# button.net
KiCad netlist of a schematic drawn in EAGLE
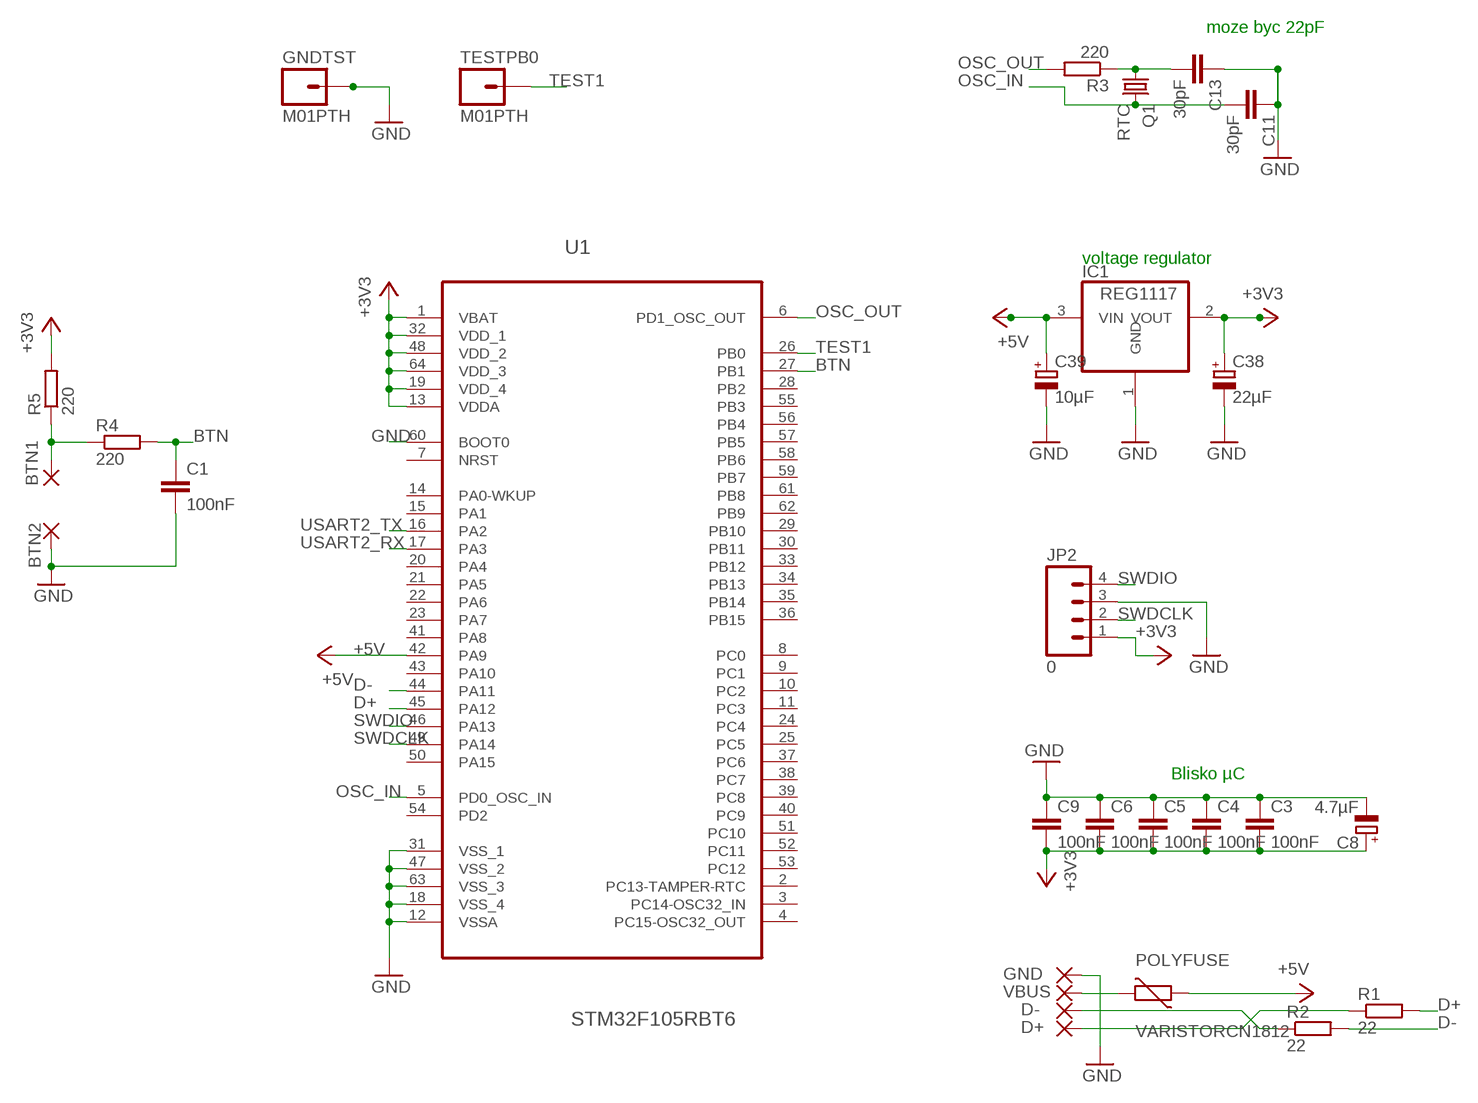
[diagram p0: schematic, sheet 1]

(export (version "E")
  (design (tool "Eeschema 10.0.6"))
  (components
    (comp (ref "BTN1")
      (value "1,6/0,8")
      (footprint "eagle-import:1,6_0,8")
      (libsource (lib "eagle-import") (part "1,6/0,8"))
    )
    (comp (ref "BTN2")
      (value "1,6/0,8")
      (footprint "eagle-import:1,6_0,8")
      (libsource (lib "eagle-import") (part "1,6/0,8"))
    )
    (comp (ref "C1")
      (value "100nF")
      (footprint "eagle-import:C0603")
      (libsource (lib "eagle-import") (part "C-EUC0603"))
    )
    (comp (ref "C3")
      (value "100nF")
      (footprint "eagle-import:C0603")
      (libsource (lib "eagle-import") (part "C-EUC0603"))
    )
    (comp (ref "C4")
      (value "100nF")
      (footprint "eagle-import:C0603")
      (libsource (lib "eagle-import") (part "C-EUC0603"))
    )
    (comp (ref "C5")
      (value "100nF")
      (footprint "eagle-import:C0603")
      (libsource (lib "eagle-import") (part "C-EUC0603"))
    )
    (comp (ref "C6")
      (value "100nF")
      (footprint "eagle-import:C0603")
      (libsource (lib "eagle-import") (part "C-EUC0603"))
    )
    (comp (ref "C8")
      (value "4.7µF")
      (footprint "eagle-import:A_3216-18R")
      (libsource (lib "eagle-import") (part "CPOL-EUA/3216-18R"))
    )
    (comp (ref "C9")
      (value "100nF")
      (footprint "eagle-import:C0603")
      (libsource (lib "eagle-import") (part "C-EUC0603"))
    )
    (comp (ref "C11")
      (value "30pF")
      (footprint "eagle-import:C0603")
      (libsource (lib "eagle-import") (part "C-EUC0603"))
    )
    (comp (ref "C13")
      (value "30pF")
      (footprint "eagle-import:C0603")
      (libsource (lib "eagle-import") (part "C-EUC0603"))
    )
    (comp (ref "C38")
      (value "22µF")
      (footprint "eagle-import:B_3528-21W")
      (libsource (lib "eagle-import") (part "CPOL-EUB/3528-21W"))
    )
    (comp (ref "C39")
      (value "10µF")
      (footprint "eagle-import:B_3528-21W")
      (libsource (lib "eagle-import") (part "CPOL-EUB/3528-21W"))
    )
    (comp (ref "D+")
      (value "1,6/0,8")
      (footprint "eagle-import:1,6_0,8")
      (libsource (lib "eagle-import") (part "1,6/0,8"))
    )
    (comp (ref "D-")
      (value "1,6/0,8")
      (footprint "eagle-import:1,6_0,8")
      (libsource (lib "eagle-import") (part "1,6/0,8"))
    )
    (comp (ref "GND")
      (value "1,6/0,8")
      (footprint "eagle-import:1,6_0,8")
      (libsource (lib "eagle-import") (part "1,6/0,8"))
    )
    (comp (ref "GNDTST")
      (value "M01PTH")
      (footprint "eagle-import:1X01")
      (libsource (lib "eagle-import") (part "M01PTH"))
    )
    (comp (ref "IC1")
      (value "REG1117")
      (footprint "eagle-import:SOT223")
      (libsource (lib "eagle-import") (part "REG1117"))
    )
    (comp (ref "JP2")
      (value "0")
      (footprint "eagle-import:1X04")
      (libsource (lib "eagle-import") (part "M04PTH"))
    )
    (comp (ref "POLYFUSE")
      (value "VARISTORCN1812")
      (footprint "eagle-import:CT_CN1812")
      (libsource (lib "eagle-import") (part "VARISTORCN1812"))
    )
    (comp (ref "Q1")
      (value "RTC")
      (footprint "eagle-import:HC49_S")
      (libsource (lib "eagle-import") (part "CRYSTALHC49S"))
    )
    (comp (ref "R1")
      (value "22")
      (footprint "eagle-import:R0805")
      (libsource (lib "eagle-import") (part "resistor_R-EU_R0805"))
    )
    (comp (ref "R2")
      (value "22")
      (footprint "eagle-import:R0805")
      (libsource (lib "eagle-import") (part "resistor_R-EU_R0805"))
    )
    (comp (ref "R3")
      (value "220")
      (footprint "eagle-import:R0603")
      (libsource (lib "eagle-import") (part "R-EU_R0603"))
    )
    (comp (ref "R4")
      (value "220")
      (footprint "eagle-import:R0603")
      (libsource (lib "eagle-import") (part "R-EU_R0603"))
    )
    (comp (ref "R5")
      (value "220")
      (footprint "eagle-import:R0603")
      (libsource (lib "eagle-import") (part "R-EU_R0603"))
    )
    (comp (ref "TESTPB0")
      (value "M01PTH")
      (footprint "eagle-import:1X01")
      (libsource (lib "eagle-import") (part "M01PTH"))
    )
    (comp (ref "U1")
      (value "STM32F105RBT6")
      (footprint "eagle-import:QFP50P1200X1200X160-64N")
      (libsource (lib "eagle-import") (part "STM32F105RBT6"))
    )
    (comp (ref "VBUS")
      (value "1,6/0,8")
      (footprint "eagle-import:1,6_0,8")
      (libsource (lib "eagle-import") (part "1,6/0,8"))
    )
  )
  (nets
    (net (code "1") (name "+3V3") (class "Default")
      (node (ref "C3") (pin "2") (pinfunction "2_2") (pintype "passive"))
      (node (ref "C38") (pin "+") (pinfunction "+_+") (pintype "passive"))
      (node (ref "C4") (pin "2") (pinfunction "2_2") (pintype "passive"))
      (node (ref "C5") (pin "2") (pinfunction "2_2") (pintype "passive"))
      (node (ref "C6") (pin "2") (pinfunction "2_2") (pintype "passive"))
      (node (ref "C8") (pin "+") (pinfunction "+_+") (pintype "passive"))
      (node (ref "C9") (pin "2") (pinfunction "2_2") (pintype "passive"))
      (node (ref "IC1") (pin "2") (pinfunction "VOUT_2") (pintype "output"))
      (node (ref "JP2") (pin "1") (pinfunction "1_1") (pintype "passive"))
      (node (ref "R5") (pin "2") (pinfunction "2_2") (pintype "passive"))
      (node (ref "U1") (pin "1") (pinfunction "VBAT_1") (pintype "power_in"))
      (node (ref "U1") (pin "13") (pinfunction "VDDA_13") (pintype "power_in"))
      (node (ref "U1") (pin "19") (pinfunction "VDD_4_19") (pintype "power_in"))
      (node (ref "U1") (pin "32") (pinfunction "VDD_1_32") (pintype "power_in"))
      (node (ref "U1") (pin "48") (pinfunction "VDD_2_48") (pintype "power_in"))
      (node (ref "U1") (pin "64") (pinfunction "VDD_3_64") (pintype "power_in"))
    )
    (net (code "2") (name "+5V") (class "Default")
      (node (ref "C39") (pin "+") (pinfunction "+_+") (pintype "passive"))
      (node (ref "IC1") (pin "3") (pinfunction "VIN_3") (pintype "input"))
      (node (ref "POLYFUSE") (pin "1") (pinfunction "1_1") (pintype "passive"))
      (node (ref "U1") (pin "42") (pinfunction "PA9_42") (pintype "bidirectional"))
    )
    (net (code "3") (name "/BTN") (class "Default")
      (node (ref "C1") (pin "1") (pinfunction "1_1") (pintype "passive"))
      (node (ref "R4") (pin "2") (pinfunction "2_2") (pintype "passive"))
      (node (ref "U1") (pin "27") (pinfunction "PB1_27") (pintype "bidirectional"))
    )
    (net (code "4") (name "/D+") (class "Default")
      (node (ref "R1") (pin "2") (pinfunction "2_2") (pintype "passive"))
      (node (ref "U1") (pin "45") (pinfunction "PA12_45") (pintype "bidirectional"))
    )
    (net (code "5") (name "/D-") (class "Default")
      (node (ref "R2") (pin "2") (pinfunction "2_2") (pintype "passive"))
      (node (ref "U1") (pin "44") (pinfunction "PA11_44") (pintype "bidirectional"))
    )
    (net (code "6") (name "/OSC_IN") (class "Default")
      (node (ref "C11") (pin "2") (pinfunction "2_2") (pintype "passive"))
      (node (ref "Q1") (pin "2") (pinfunction "2_2") (pintype "passive"))
      (node (ref "U1") (pin "5") (pinfunction "PD0_OSC_IN_5") (pintype "bidirectional"))
    )
    (net (code "7") (name "/OSC_OUT") (class "Default")
      (node (ref "R3") (pin "2") (pinfunction "2_2") (pintype "passive"))
      (node (ref "U1") (pin "6") (pinfunction "PD1_OSC_OUT_6") (pintype "bidirectional"))
    )
    (net (code "8") (name "/SWDCLK") (class "Default")
      (node (ref "JP2") (pin "2") (pinfunction "2_2") (pintype "passive"))
      (node (ref "U1") (pin "49") (pinfunction "PA14_49") (pintype "bidirectional"))
    )
    (net (code "9") (name "/SWDIO") (class "Default")
      (node (ref "JP2") (pin "4") (pinfunction "4_4") (pintype "passive"))
      (node (ref "U1") (pin "46") (pinfunction "PA13_46") (pintype "bidirectional"))
    )
    (net (code "10") (name "/TEST1") (class "Default")
      (node (ref "TESTPB0") (pin "1") (pinfunction "1_1") (pintype "passive"))
      (node (ref "U1") (pin "26") (pinfunction "PB0_26") (pintype "bidirectional"))
    )
    (net (code "11") (name "/USART2_RX") (class "Default")
      (node (ref "U1") (pin "17") (pinfunction "PA3_17") (pintype "bidirectional"))
    )
    (net (code "12") (name "/USART2_TX") (class "Default")
      (node (ref "U1") (pin "16") (pinfunction "PA2_16") (pintype "bidirectional"))
    )
    (net (code "13") (name "GND") (class "Default")
      (node (ref "BTN2") (pin "1") (pinfunction "P_1") (pintype "passive"))
      (node (ref "C1") (pin "2") (pinfunction "2_2") (pintype "passive"))
      (node (ref "C11") (pin "1") (pinfunction "1_1") (pintype "passive"))
      (node (ref "C13") (pin "1") (pinfunction "1_1") (pintype "passive"))
      (node (ref "C3") (pin "1") (pinfunction "1_1") (pintype "passive"))
      (node (ref "C38") (pin "-") (pinfunction "-_-") (pintype "passive"))
      (node (ref "C39") (pin "-") (pinfunction "-_-") (pintype "passive"))
      (node (ref "C4") (pin "1") (pinfunction "1_1") (pintype "passive"))
      (node (ref "C5") (pin "1") (pinfunction "1_1") (pintype "passive"))
      (node (ref "C6") (pin "1") (pinfunction "1_1") (pintype "passive"))
      (node (ref "C8") (pin "-") (pinfunction "-_-") (pintype "passive"))
      (node (ref "C9") (pin "1") (pinfunction "1_1") (pintype "passive"))
      (node (ref "GND") (pin "1") (pinfunction "P_1") (pintype "passive"))
      (node (ref "GNDTST") (pin "1") (pinfunction "1_1") (pintype "passive"))
      (node (ref "IC1") (pin "1") (pinfunction "GND_1") (pintype "power_in"))
      (node (ref "JP2") (pin "3") (pinfunction "3_3") (pintype "passive"))
      (node (ref "U1") (pin "12") (pinfunction "VSSA_12") (pintype "power_in"))
      (node (ref "U1") (pin "18") (pinfunction "VSS_4_18") (pintype "power_in"))
      (node (ref "U1") (pin "31") (pinfunction "VSS_1_31") (pintype "power_in"))
      (node (ref "U1") (pin "47") (pinfunction "VSS_2_47") (pintype "power_in"))
      (node (ref "U1") (pin "60") (pinfunction "BOOT0_60") (pintype "input"))
      (node (ref "U1") (pin "63") (pinfunction "VSS_3_63") (pintype "power_in"))
    )
    (net (code "14") (name "Net-(BTN1-P)") (class "Default")
      (node (ref "BTN1") (pin "1") (pinfunction "P_1") (pintype "passive"))
      (node (ref "R4") (pin "1") (pinfunction "1_1") (pintype "passive"))
      (node (ref "R5") (pin "1") (pinfunction "1_1") (pintype "passive"))
    )
    (net (code "15") (name "Net-(C13-Pad2)") (class "Default")
      (node (ref "C13") (pin "2") (pinfunction "2_2") (pintype "passive"))
      (node (ref "Q1") (pin "1") (pinfunction "1_1") (pintype "passive"))
      (node (ref "R3") (pin "1") (pinfunction "1_1") (pintype "passive"))
    )
    (net (code "16") (name "Net-(D+-P)") (class "Default")
      (node (ref "D+") (pin "1") (pinfunction "P_1") (pintype "passive"))
      (node (ref "R1") (pin "1") (pinfunction "1_1") (pintype "passive"))
    )
    (net (code "17") (name "Net-(D--P)") (class "Default")
      (node (ref "D-") (pin "1") (pinfunction "P_1") (pintype "passive"))
      (node (ref "R2") (pin "1") (pinfunction "1_1") (pintype "passive"))
    )
    (net (code "18") (name "Net-(VBUS-P)") (class "Default")
      (node (ref "POLYFUSE") (pin "2") (pinfunction "2_2") (pintype "passive"))
      (node (ref "VBUS") (pin "1") (pinfunction "P_1") (pintype "passive"))
    )
    (net (code "19") (name "unconnected-(U1-NRST-Pad7)") (class "Default")
      (node (ref "U1") (pin "7") (pinfunction "NRST_7") (pintype "bidirectional"))
    )
    (net (code "20") (name "unconnected-(U1-PA0-WKUP-Pad14)") (class "Default")
      (node (ref "U1") (pin "14") (pinfunction "PA0-WKUP_14") (pintype "bidirectional"))
    )
    (net (code "21") (name "unconnected-(U1-PA1-Pad15)") (class "Default")
      (node (ref "U1") (pin "15") (pinfunction "PA1_15") (pintype "bidirectional"))
    )
    (net (code "22") (name "unconnected-(U1-PA4-Pad20)") (class "Default")
      (node (ref "U1") (pin "20") (pinfunction "PA4_20") (pintype "bidirectional"))
    )
    (net (code "23") (name "unconnected-(U1-PA5-Pad21)") (class "Default")
      (node (ref "U1") (pin "21") (pinfunction "PA5_21") (pintype "bidirectional"))
    )
    (net (code "24") (name "unconnected-(U1-PA6-Pad22)") (class "Default")
      (node (ref "U1") (pin "22") (pinfunction "PA6_22") (pintype "bidirectional"))
    )
    (net (code "25") (name "unconnected-(U1-PA7-Pad23)") (class "Default")
      (node (ref "U1") (pin "23") (pinfunction "PA7_23") (pintype "bidirectional"))
    )
    (net (code "26") (name "unconnected-(U1-PA8-Pad41)") (class "Default")
      (node (ref "U1") (pin "41") (pinfunction "PA8_41") (pintype "bidirectional"))
    )
    (net (code "27") (name "unconnected-(U1-PA10-Pad43)") (class "Default")
      (node (ref "U1") (pin "43") (pinfunction "PA10_43") (pintype "bidirectional"))
    )
    (net (code "28") (name "unconnected-(U1-PA15-Pad50)") (class "Default")
      (node (ref "U1") (pin "50") (pinfunction "PA15_50") (pintype "bidirectional"))
    )
    (net (code "29") (name "unconnected-(U1-PB2-Pad28)") (class "Default")
      (node (ref "U1") (pin "28") (pinfunction "PB2_28") (pintype "bidirectional"))
    )
    (net (code "30") (name "unconnected-(U1-PB3-Pad55)") (class "Default")
      (node (ref "U1") (pin "55") (pinfunction "PB3_55") (pintype "bidirectional"))
    )
    (net (code "31") (name "unconnected-(U1-PB4-Pad56)") (class "Default")
      (node (ref "U1") (pin "56") (pinfunction "PB4_56") (pintype "bidirectional"))
    )
    (net (code "32") (name "unconnected-(U1-PB5-Pad57)") (class "Default")
      (node (ref "U1") (pin "57") (pinfunction "PB5_57") (pintype "bidirectional"))
    )
    (net (code "33") (name "unconnected-(U1-PB6-Pad58)") (class "Default")
      (node (ref "U1") (pin "58") (pinfunction "PB6_58") (pintype "bidirectional"))
    )
    (net (code "34") (name "unconnected-(U1-PB7-Pad59)") (class "Default")
      (node (ref "U1") (pin "59") (pinfunction "PB7_59") (pintype "bidirectional"))
    )
    (net (code "35") (name "unconnected-(U1-PB8-Pad61)") (class "Default")
      (node (ref "U1") (pin "61") (pinfunction "PB8_61") (pintype "bidirectional"))
    )
    (net (code "36") (name "unconnected-(U1-PB9-Pad62)") (class "Default")
      (node (ref "U1") (pin "62") (pinfunction "PB9_62") (pintype "bidirectional"))
    )
    (net (code "37") (name "unconnected-(U1-PB10-Pad29)") (class "Default")
      (node (ref "U1") (pin "29") (pinfunction "PB10_29") (pintype "bidirectional"))
    )
    (net (code "38") (name "unconnected-(U1-PB11-Pad30)") (class "Default")
      (node (ref "U1") (pin "30") (pinfunction "PB11_30") (pintype "bidirectional"))
    )
    (net (code "39") (name "unconnected-(U1-PB12-Pad33)") (class "Default")
      (node (ref "U1") (pin "33") (pinfunction "PB12_33") (pintype "bidirectional"))
    )
    (net (code "40") (name "unconnected-(U1-PB13-Pad34)") (class "Default")
      (node (ref "U1") (pin "34") (pinfunction "PB13_34") (pintype "bidirectional"))
    )
    (net (code "41") (name "unconnected-(U1-PB14-Pad35)") (class "Default")
      (node (ref "U1") (pin "35") (pinfunction "PB14_35") (pintype "bidirectional"))
    )
    (net (code "42") (name "unconnected-(U1-PB15-Pad36)") (class "Default")
      (node (ref "U1") (pin "36") (pinfunction "PB15_36") (pintype "bidirectional"))
    )
    (net (code "43") (name "unconnected-(U1-PC0-Pad8)") (class "Default")
      (node (ref "U1") (pin "8") (pinfunction "PC0_8") (pintype "bidirectional"))
    )
    (net (code "44") (name "unconnected-(U1-PC1-Pad9)") (class "Default")
      (node (ref "U1") (pin "9") (pinfunction "PC1_9") (pintype "bidirectional"))
    )
    (net (code "45") (name "unconnected-(U1-PC2-Pad10)") (class "Default")
      (node (ref "U1") (pin "10") (pinfunction "PC2_10") (pintype "bidirectional"))
    )
    (net (code "46") (name "unconnected-(U1-PC3-Pad11)") (class "Default")
      (node (ref "U1") (pin "11") (pinfunction "PC3_11") (pintype "bidirectional"))
    )
    (net (code "47") (name "unconnected-(U1-PC4-Pad24)") (class "Default")
      (node (ref "U1") (pin "24") (pinfunction "PC4_24") (pintype "bidirectional"))
    )
    (net (code "48") (name "unconnected-(U1-PC5-Pad25)") (class "Default")
      (node (ref "U1") (pin "25") (pinfunction "PC5_25") (pintype "bidirectional"))
    )
    (net (code "49") (name "unconnected-(U1-PC6-Pad37)") (class "Default")
      (node (ref "U1") (pin "37") (pinfunction "PC6_37") (pintype "bidirectional"))
    )
    (net (code "50") (name "unconnected-(U1-PC7-Pad38)") (class "Default")
      (node (ref "U1") (pin "38") (pinfunction "PC7_38") (pintype "bidirectional"))
    )
    (net (code "51") (name "unconnected-(U1-PC8-Pad39)") (class "Default")
      (node (ref "U1") (pin "39") (pinfunction "PC8_39") (pintype "bidirectional"))
    )
    (net (code "52") (name "unconnected-(U1-PC9-Pad40)") (class "Default")
      (node (ref "U1") (pin "40") (pinfunction "PC9_40") (pintype "bidirectional"))
    )
    (net (code "53") (name "unconnected-(U1-PC10-Pad51)") (class "Default")
      (node (ref "U1") (pin "51") (pinfunction "PC10_51") (pintype "bidirectional"))
    )
    (net (code "54") (name "unconnected-(U1-PC11-Pad52)") (class "Default")
      (node (ref "U1") (pin "52") (pinfunction "PC11_52") (pintype "bidirectional"))
    )
    (net (code "55") (name "unconnected-(U1-PC12-Pad53)") (class "Default")
      (node (ref "U1") (pin "53") (pinfunction "PC12_53") (pintype "bidirectional"))
    )
    (net (code "56") (name "unconnected-(U1-PC13-TAMPER-RTC-Pad2)") (class "Default")
      (node (ref "U1") (pin "2") (pinfunction "PC13-TAMPER-RTC_2") (pintype "bidirectional"))
    )
    (net (code "57") (name "unconnected-(U1-PC14-OSC32_IN-Pad3)") (class "Default")
      (node (ref "U1") (pin "3") (pinfunction "PC14-OSC32_IN_3") (pintype "bidirectional"))
    )
    (net (code "58") (name "unconnected-(U1-PC15-OSC32_OUT-Pad4)") (class "Default")
      (node (ref "U1") (pin "4") (pinfunction "PC15-OSC32_OUT_4") (pintype "bidirectional"))
    )
    (net (code "59") (name "unconnected-(U1-PD2-Pad54)") (class "Default")
      (node (ref "U1") (pin "54") (pinfunction "PD2_54") (pintype "bidirectional"))
    )
  )
)
